# arcaduinome.net
KiCad netlist of a schematic drawn in EAGLE
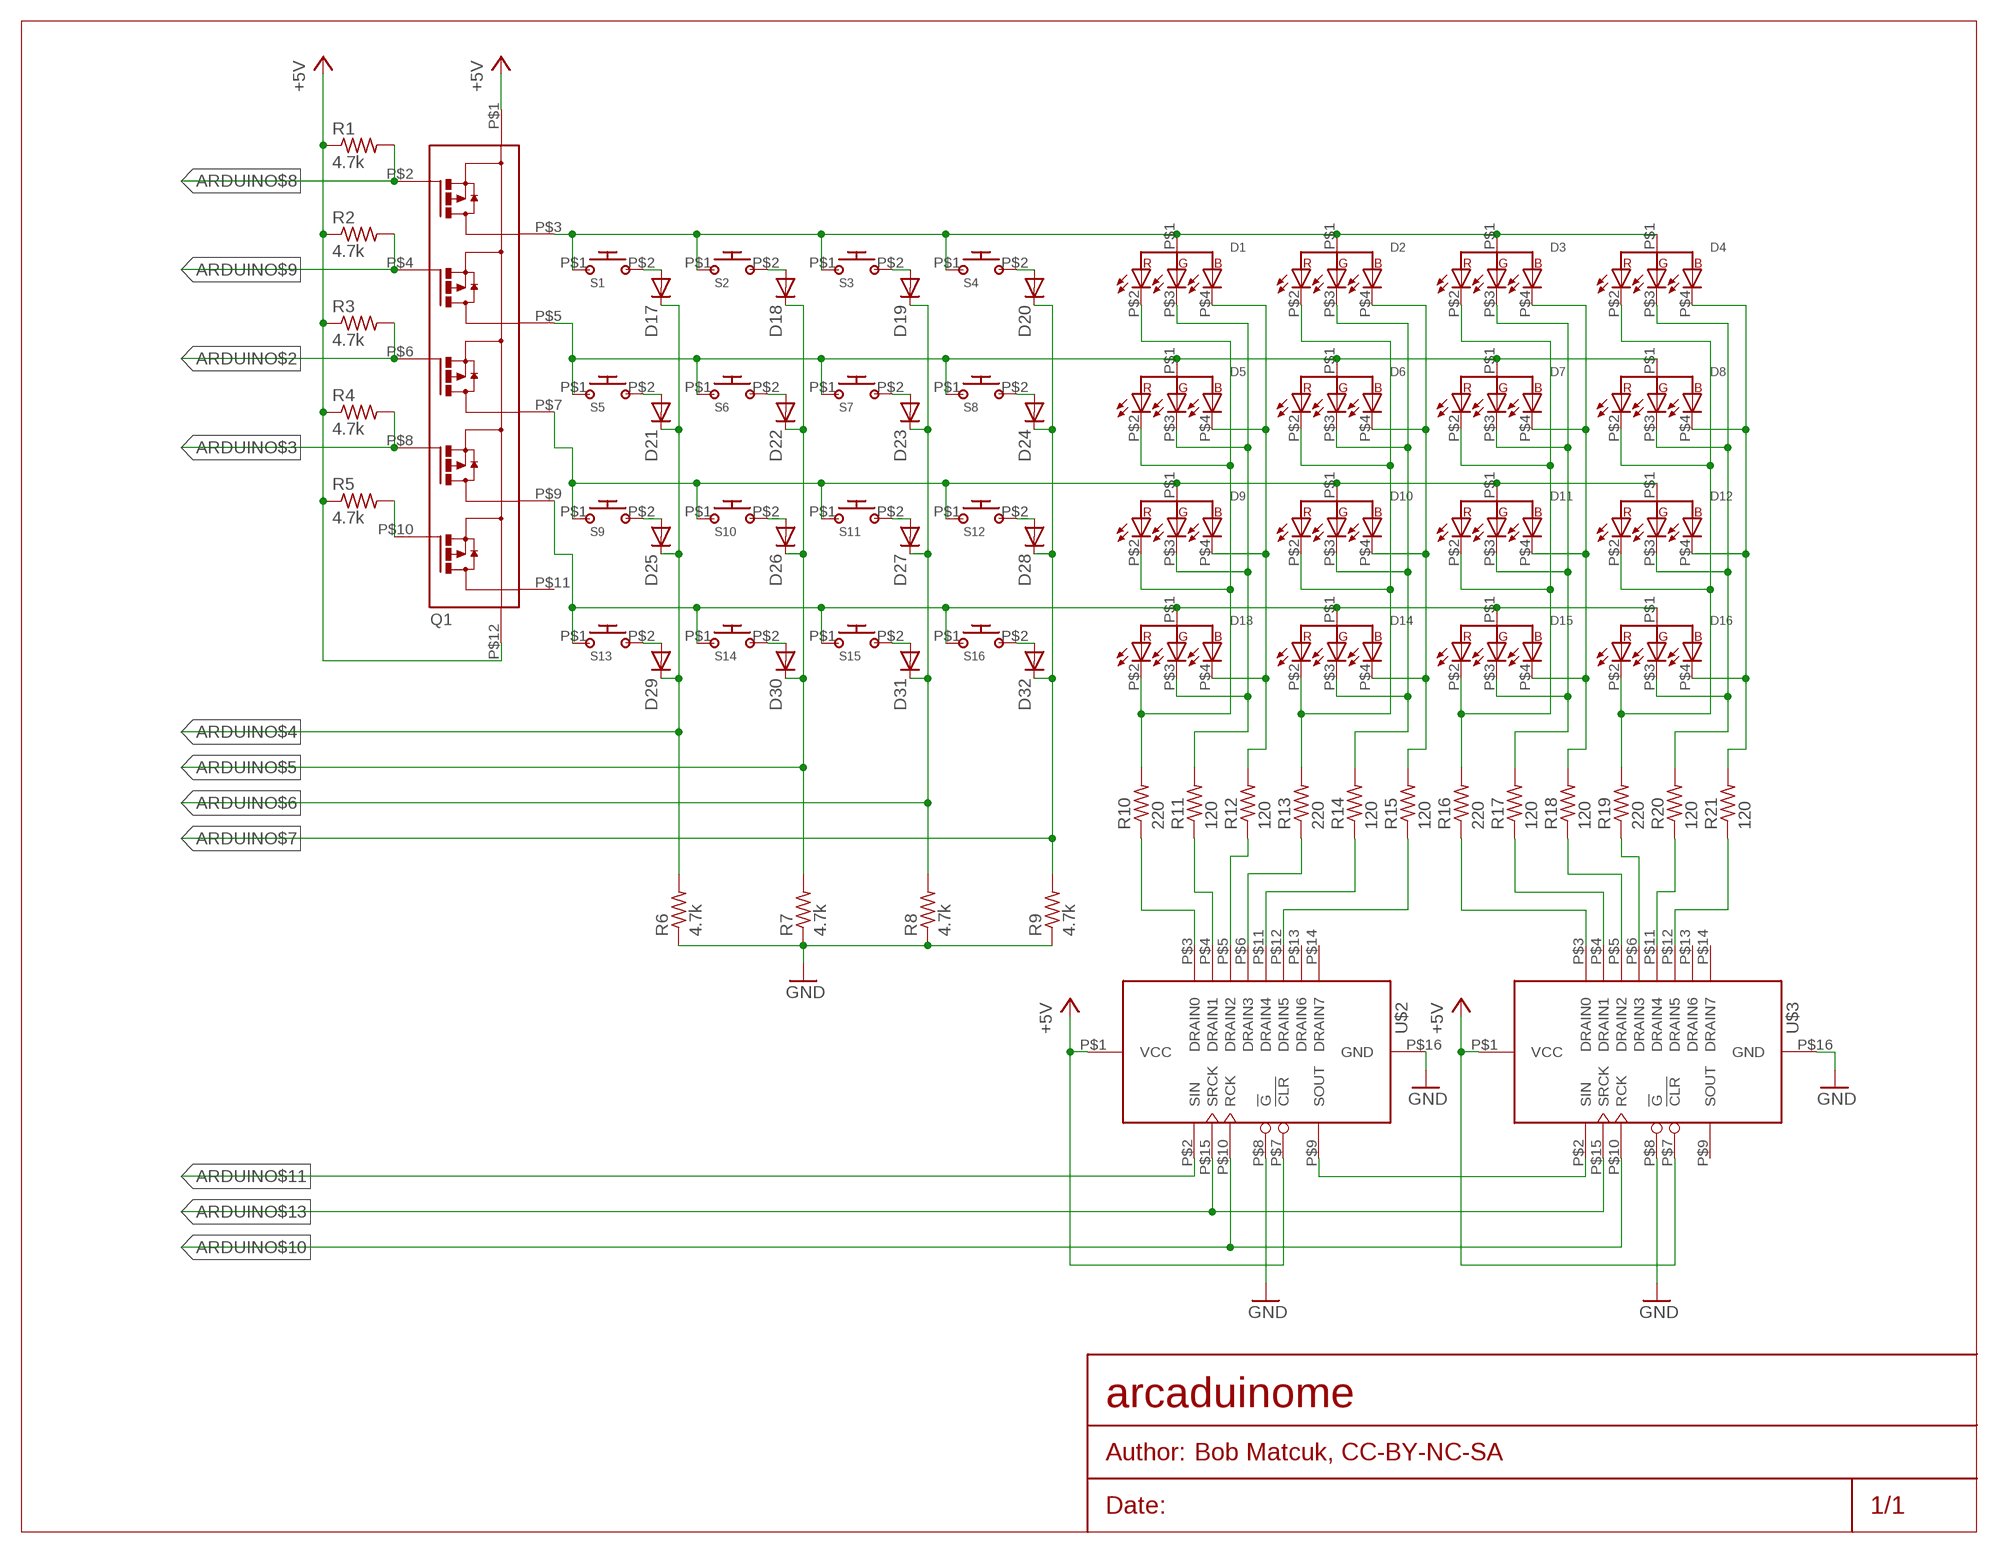
[diagram p0: schematic, sheet 1]

(export (version "E")
  (design (tool "Eeschema 10.0.6"))
  (components
    (comp (ref "D1")
      (value "FD-5WSRGB-A")
      (footprint "eagle-import:5MM_RGB_LED")
      (libsource (lib "eagle-import") (part "FD-5WSRGB-A"))
    )
    (comp (ref "D2")
      (value "FD-5WSRGB-A")
      (footprint "eagle-import:5MM_RGB_LED")
      (libsource (lib "eagle-import") (part "FD-5WSRGB-A"))
    )
    (comp (ref "D3")
      (value "FD-5WSRGB-A")
      (footprint "eagle-import:5MM_RGB_LED")
      (libsource (lib "eagle-import") (part "FD-5WSRGB-A"))
    )
    (comp (ref "D4")
      (value "FD-5WSRGB-A")
      (footprint "eagle-import:5MM_RGB_LED")
      (libsource (lib "eagle-import") (part "FD-5WSRGB-A"))
    )
    (comp (ref "D5")
      (value "FD-5WSRGB-A")
      (footprint "eagle-import:5MM_RGB_LED")
      (libsource (lib "eagle-import") (part "FD-5WSRGB-A"))
    )
    (comp (ref "D6")
      (value "FD-5WSRGB-A")
      (footprint "eagle-import:5MM_RGB_LED")
      (libsource (lib "eagle-import") (part "FD-5WSRGB-A"))
    )
    (comp (ref "D7")
      (value "FD-5WSRGB-A")
      (footprint "eagle-import:5MM_RGB_LED")
      (libsource (lib "eagle-import") (part "FD-5WSRGB-A"))
    )
    (comp (ref "D8")
      (value "FD-5WSRGB-A")
      (footprint "eagle-import:5MM_RGB_LED")
      (libsource (lib "eagle-import") (part "FD-5WSRGB-A"))
    )
    (comp (ref "D9")
      (value "FD-5WSRGB-A")
      (footprint "eagle-import:5MM_RGB_LED")
      (libsource (lib "eagle-import") (part "FD-5WSRGB-A"))
    )
    (comp (ref "D10")
      (value "FD-5WSRGB-A")
      (footprint "eagle-import:5MM_RGB_LED")
      (libsource (lib "eagle-import") (part "FD-5WSRGB-A"))
    )
    (comp (ref "D11")
      (value "FD-5WSRGB-A")
      (footprint "eagle-import:5MM_RGB_LED")
      (libsource (lib "eagle-import") (part "FD-5WSRGB-A"))
    )
    (comp (ref "D12")
      (value "FD-5WSRGB-A")
      (footprint "eagle-import:5MM_RGB_LED")
      (libsource (lib "eagle-import") (part "FD-5WSRGB-A"))
    )
    (comp (ref "D13")
      (value "FD-5WSRGB-A")
      (footprint "eagle-import:5MM_RGB_LED")
      (libsource (lib "eagle-import") (part "FD-5WSRGB-A"))
    )
    (comp (ref "D14")
      (value "FD-5WSRGB-A")
      (footprint "eagle-import:5MM_RGB_LED")
      (libsource (lib "eagle-import") (part "FD-5WSRGB-A"))
    )
    (comp (ref "D15")
      (value "FD-5WSRGB-A")
      (footprint "eagle-import:5MM_RGB_LED")
      (libsource (lib "eagle-import") (part "FD-5WSRGB-A"))
    )
    (comp (ref "D16")
      (value "FD-5WSRGB-A")
      (footprint "eagle-import:5MM_RGB_LED")
      (libsource (lib "eagle-import") (part "FD-5WSRGB-A"))
    )
    (comp (ref "D17")
      (value "1N4148DO35-7")
      (footprint "eagle-import:DO35-7")
      (libsource (lib "eagle-import") (part "1N4148DO35-7"))
    )
    (comp (ref "D18")
      (value "1N4148DO35-7")
      (footprint "eagle-import:DO35-7")
      (libsource (lib "eagle-import") (part "1N4148DO35-7"))
    )
    (comp (ref "D19")
      (value "1N4148DO35-7")
      (footprint "eagle-import:DO35-7")
      (libsource (lib "eagle-import") (part "1N4148DO35-7"))
    )
    (comp (ref "D20")
      (value "1N4148DO35-7")
      (footprint "eagle-import:DO35-7")
      (libsource (lib "eagle-import") (part "1N4148DO35-7"))
    )
    (comp (ref "D21")
      (value "1N4148DO35-7")
      (footprint "eagle-import:DO35-7")
      (libsource (lib "eagle-import") (part "1N4148DO35-7"))
    )
    (comp (ref "D22")
      (value "1N4148DO35-7")
      (footprint "eagle-import:DO35-7")
      (libsource (lib "eagle-import") (part "1N4148DO35-7"))
    )
    (comp (ref "D23")
      (value "1N4148DO35-7")
      (footprint "eagle-import:DO35-7")
      (libsource (lib "eagle-import") (part "1N4148DO35-7"))
    )
    (comp (ref "D24")
      (value "1N4148DO35-7")
      (footprint "eagle-import:DO35-7")
      (libsource (lib "eagle-import") (part "1N4148DO35-7"))
    )
    (comp (ref "D25")
      (value "1N4148DO35-7")
      (footprint "eagle-import:DO35-7")
      (libsource (lib "eagle-import") (part "1N4148DO35-7"))
    )
    (comp (ref "D26")
      (value "1N4148DO35-7")
      (footprint "eagle-import:DO35-7")
      (libsource (lib "eagle-import") (part "1N4148DO35-7"))
    )
    (comp (ref "D27")
      (value "1N4148DO35-7")
      (footprint "eagle-import:DO35-7")
      (libsource (lib "eagle-import") (part "1N4148DO35-7"))
    )
    (comp (ref "D28")
      (value "1N4148DO35-7")
      (footprint "eagle-import:DO35-7")
      (libsource (lib "eagle-import") (part "1N4148DO35-7"))
    )
    (comp (ref "D29")
      (value "1N4148DO35-7")
      (footprint "eagle-import:DO35-7")
      (libsource (lib "eagle-import") (part "1N4148DO35-7"))
    )
    (comp (ref "D30")
      (value "1N4148DO35-7")
      (footprint "eagle-import:DO35-7")
      (libsource (lib "eagle-import") (part "1N4148DO35-7"))
    )
    (comp (ref "D31")
      (value "1N4148DO35-7")
      (footprint "eagle-import:DO35-7")
      (libsource (lib "eagle-import") (part "1N4148DO35-7"))
    )
    (comp (ref "D32")
      (value "1N4148DO35-7")
      (footprint "eagle-import:DO35-7")
      (libsource (lib "eagle-import") (part "1N4148DO35-7"))
    )
    (comp (ref "Q1")
      (value "SLA5086")
      (footprint "eagle-import:SLA12")
      (libsource (lib "eagle-import") (part "SLA5086"))
    )
    (comp (ref "R1")
      (value "4.7k")
      (footprint "eagle-import:0207_10")
      (libsource (lib "eagle-import") (part "R-US_0207/10"))
    )
    (comp (ref "R2")
      (value "4.7k")
      (footprint "eagle-import:0207_10")
      (libsource (lib "eagle-import") (part "R-US_0207/10"))
    )
    (comp (ref "R3")
      (value "4.7k")
      (footprint "eagle-import:0207_10")
      (libsource (lib "eagle-import") (part "R-US_0207/10"))
    )
    (comp (ref "R4")
      (value "4.7k")
      (footprint "eagle-import:0207_10")
      (libsource (lib "eagle-import") (part "R-US_0207/10"))
    )
    (comp (ref "R5")
      (value "4.7k")
      (footprint "eagle-import:0207_10")
      (libsource (lib "eagle-import") (part "R-US_0207/10"))
    )
    (comp (ref "R6")
      (value "4.7k")
      (footprint "eagle-import:0207_10")
      (libsource (lib "eagle-import") (part "R-US_0207/10"))
    )
    (comp (ref "R7")
      (value "4.7k")
      (footprint "eagle-import:0207_10")
      (libsource (lib "eagle-import") (part "R-US_0207/10"))
    )
    (comp (ref "R8")
      (value "4.7k")
      (footprint "eagle-import:0207_10")
      (libsource (lib "eagle-import") (part "R-US_0207/10"))
    )
    (comp (ref "R9")
      (value "4.7k")
      (footprint "eagle-import:0207_10")
      (libsource (lib "eagle-import") (part "R-US_0207/10"))
    )
    (comp (ref "R10")
      (value "220")
      (footprint "eagle-import:0207_7")
      (libsource (lib "eagle-import") (part "R-US_0207/7"))
    )
    (comp (ref "R11")
      (value "120")
      (footprint "eagle-import:0204_5")
      (libsource (lib "eagle-import") (part "R-US_0204/5"))
    )
    (comp (ref "R12")
      (value "120")
      (footprint "eagle-import:0204_5")
      (libsource (lib "eagle-import") (part "R-US_0204/5"))
    )
    (comp (ref "R13")
      (value "220")
      (footprint "eagle-import:0207_7")
      (libsource (lib "eagle-import") (part "R-US_0207/7"))
    )
    (comp (ref "R14")
      (value "120")
      (footprint "eagle-import:0204_5")
      (libsource (lib "eagle-import") (part "R-US_0204/5"))
    )
    (comp (ref "R15")
      (value "120")
      (footprint "eagle-import:0204_5")
      (libsource (lib "eagle-import") (part "R-US_0204/5"))
    )
    (comp (ref "R16")
      (value "220")
      (footprint "eagle-import:0207_7")
      (libsource (lib "eagle-import") (part "R-US_0207/7"))
    )
    (comp (ref "R17")
      (value "120")
      (footprint "eagle-import:0204_5")
      (libsource (lib "eagle-import") (part "R-US_0204/5"))
    )
    (comp (ref "R18")
      (value "120")
      (footprint "eagle-import:0204_5")
      (libsource (lib "eagle-import") (part "R-US_0204/5"))
    )
    (comp (ref "R19")
      (value "220")
      (footprint "eagle-import:0207_7")
      (libsource (lib "eagle-import") (part "R-US_0207/7"))
    )
    (comp (ref "R20")
      (value "120")
      (footprint "eagle-import:0204_5")
      (libsource (lib "eagle-import") (part "R-US_0204/5"))
    )
    (comp (ref "R21")
      (value "120")
      (footprint "eagle-import:0204_5")
      (libsource (lib "eagle-import") (part "R-US_0204/5"))
    )
    (comp (ref "S1")
      (value "SANWA_OBSC_24_CW")
      (footprint "eagle-import:SANWA_24MM")
      (libsource (lib "eagle-import") (part "SANWA_OBSC_24_CW"))
    )
    (comp (ref "S2")
      (value "SANWA_OBSC_24_CW")
      (footprint "eagle-import:SANWA_24MM")
      (libsource (lib "eagle-import") (part "SANWA_OBSC_24_CW"))
    )
    (comp (ref "S3")
      (value "SANWA_OBSC_24_CW")
      (footprint "eagle-import:SANWA_24MM")
      (libsource (lib "eagle-import") (part "SANWA_OBSC_24_CW"))
    )
    (comp (ref "S4")
      (value "SANWA_OBSC_24_CW")
      (footprint "eagle-import:SANWA_24MM")
      (libsource (lib "eagle-import") (part "SANWA_OBSC_24_CW"))
    )
    (comp (ref "S5")
      (value "SANWA_OBSC_24_CW")
      (footprint "eagle-import:SANWA_24MM")
      (libsource (lib "eagle-import") (part "SANWA_OBSC_24_CW"))
    )
    (comp (ref "S6")
      (value "SANWA_OBSC_24_CW")
      (footprint "eagle-import:SANWA_24MM")
      (libsource (lib "eagle-import") (part "SANWA_OBSC_24_CW"))
    )
    (comp (ref "S7")
      (value "SANWA_OBSC_24_CW")
      (footprint "eagle-import:SANWA_24MM")
      (libsource (lib "eagle-import") (part "SANWA_OBSC_24_CW"))
    )
    (comp (ref "S8")
      (value "SANWA_OBSC_24_CW")
      (footprint "eagle-import:SANWA_24MM")
      (libsource (lib "eagle-import") (part "SANWA_OBSC_24_CW"))
    )
    (comp (ref "S9")
      (value "SANWA_OBSC_24_CW")
      (footprint "eagle-import:SANWA_24MM")
      (libsource (lib "eagle-import") (part "SANWA_OBSC_24_CW"))
    )
    (comp (ref "S10")
      (value "SANWA_OBSC_24_CW")
      (footprint "eagle-import:SANWA_24MM")
      (libsource (lib "eagle-import") (part "SANWA_OBSC_24_CW"))
    )
    (comp (ref "S11")
      (value "SANWA_OBSC_24_CW")
      (footprint "eagle-import:SANWA_24MM")
      (libsource (lib "eagle-import") (part "SANWA_OBSC_24_CW"))
    )
    (comp (ref "S12")
      (value "SANWA_OBSC_24_CW")
      (footprint "eagle-import:SANWA_24MM")
      (libsource (lib "eagle-import") (part "SANWA_OBSC_24_CW"))
    )
    (comp (ref "S13")
      (value "SANWA_OBSC_24_CW")
      (footprint "eagle-import:SANWA_24MM")
      (libsource (lib "eagle-import") (part "SANWA_OBSC_24_CW"))
    )
    (comp (ref "S14")
      (value "SANWA_OBSC_24_CW")
      (footprint "eagle-import:SANWA_24MM")
      (libsource (lib "eagle-import") (part "SANWA_OBSC_24_CW"))
    )
    (comp (ref "S15")
      (value "SANWA_OBSC_24_CW")
      (footprint "eagle-import:SANWA_24MM")
      (libsource (lib "eagle-import") (part "SANWA_OBSC_24_CW"))
    )
    (comp (ref "S16")
      (value "SANWA_OBSC_24_CW")
      (footprint "eagle-import:SANWA_24MM")
      (libsource (lib "eagle-import") (part "SANWA_OBSC_24_CW"))
    )
    (comp (ref "U$2")
      (value "STPIC6D595")
      (footprint "eagle-import:DIP16")
      (libsource (lib "eagle-import") (part "STPIC6D595"))
    )
    (comp (ref "U$3")
      (value "STPIC6D595")
      (footprint "eagle-import:DIP16")
      (libsource (lib "eagle-import") (part "STPIC6D595"))
    )
  )
  (nets
    (net (code "1") (name "+5V") (class "Default")
      (node (ref "Q1") (pin "P$1") (pinfunction "S_P$1") (pintype "passive"))
      (node (ref "Q1") (pin "P$12") (pinfunction "S_P$12") (pintype "passive"))
      (node (ref "R1") (pin "1") (pinfunction "1_1") (pintype "passive"))
      (node (ref "R2") (pin "1") (pinfunction "1_1") (pintype "passive"))
      (node (ref "R3") (pin "1") (pinfunction "1_1") (pintype "passive"))
      (node (ref "R4") (pin "1") (pinfunction "1_1") (pintype "passive"))
      (node (ref "R5") (pin "1") (pinfunction "1_1") (pintype "passive"))
      (node (ref "U$2") (pin "P$1") (pinfunction "VCC_P$1") (pintype "power_in"))
      (node (ref "U$2") (pin "P$7") (pinfunction "~{CLR}_P$7") (pintype "bidirectional"))
      (node (ref "U$3") (pin "P$1") (pinfunction "VCC_P$1") (pintype "power_in"))
      (node (ref "U$3") (pin "P$7") (pinfunction "~{CLR}_P$7") (pintype "bidirectional"))
    )
    (net (code "2") (name "ARDUINO$2") (class "Default")
      (node (ref "Q1") (pin "P$6") (pinfunction "G$3_P$6") (pintype "passive"))
      (node (ref "R3") (pin "2") (pinfunction "2_2") (pintype "passive"))
    )
    (net (code "3") (name "ARDUINO$3") (class "Default")
      (node (ref "Q1") (pin "P$8") (pinfunction "G$4_P$8") (pintype "passive"))
      (node (ref "R4") (pin "2") (pinfunction "2_2") (pintype "passive"))
    )
    (net (code "4") (name "ARDUINO$4") (class "Default")
      (node (ref "D17") (pin "C") (pinfunction "C_C") (pintype "passive"))
      (node (ref "D21") (pin "C") (pinfunction "C_C") (pintype "passive"))
      (node (ref "D25") (pin "C") (pinfunction "C_C") (pintype "passive"))
      (node (ref "D29") (pin "C") (pinfunction "C_C") (pintype "passive"))
      (node (ref "R6") (pin "2") (pinfunction "2_2") (pintype "passive"))
    )
    (net (code "5") (name "ARDUINO$5") (class "Default")
      (node (ref "D18") (pin "C") (pinfunction "C_C") (pintype "passive"))
      (node (ref "D22") (pin "C") (pinfunction "C_C") (pintype "passive"))
      (node (ref "D26") (pin "C") (pinfunction "C_C") (pintype "passive"))
      (node (ref "D30") (pin "C") (pinfunction "C_C") (pintype "passive"))
      (node (ref "R7") (pin "2") (pinfunction "2_2") (pintype "passive"))
    )
    (net (code "6") (name "ARDUINO$6") (class "Default")
      (node (ref "D19") (pin "C") (pinfunction "C_C") (pintype "passive"))
      (node (ref "D23") (pin "C") (pinfunction "C_C") (pintype "passive"))
      (node (ref "D27") (pin "C") (pinfunction "C_C") (pintype "passive"))
      (node (ref "D31") (pin "C") (pinfunction "C_C") (pintype "passive"))
      (node (ref "R8") (pin "2") (pinfunction "2_2") (pintype "passive"))
    )
    (net (code "7") (name "ARDUINO$7") (class "Default")
      (node (ref "D20") (pin "C") (pinfunction "C_C") (pintype "passive"))
      (node (ref "D24") (pin "C") (pinfunction "C_C") (pintype "passive"))
      (node (ref "D28") (pin "C") (pinfunction "C_C") (pintype "passive"))
      (node (ref "D32") (pin "C") (pinfunction "C_C") (pintype "passive"))
      (node (ref "R9") (pin "2") (pinfunction "2_2") (pintype "passive"))
    )
    (net (code "8") (name "ARDUINO$8") (class "Default")
      (node (ref "Q1") (pin "P$2") (pinfunction "G$1_P$2") (pintype "passive"))
      (node (ref "R1") (pin "2") (pinfunction "2_2") (pintype "passive"))
    )
    (net (code "9") (name "ARDUINO$9") (class "Default")
      (node (ref "Q1") (pin "P$4") (pinfunction "G$2_P$4") (pintype "passive"))
      (node (ref "R2") (pin "2") (pinfunction "2_2") (pintype "passive"))
    )
    (net (code "10") (name "ARDUINO$10") (class "Default")
      (node (ref "U$2") (pin "P$10") (pinfunction "RCK_P$10") (pintype "input"))
      (node (ref "U$3") (pin "P$10") (pinfunction "RCK_P$10") (pintype "input"))
    )
    (net (code "11") (name "ARDUINO$11") (class "Default")
      (node (ref "U$2") (pin "P$2") (pinfunction "SIN_P$2") (pintype "input"))
    )
    (net (code "12") (name "ARDUINO$13") (class "Default")
      (node (ref "U$2") (pin "P$15") (pinfunction "SRCK_P$15") (pintype "input"))
      (node (ref "U$3") (pin "P$15") (pinfunction "SRCK_P$15") (pintype "input"))
    )
    (net (code "13") (name "GND") (class "Default")
      (node (ref "R6") (pin "1") (pinfunction "1_1") (pintype "passive"))
      (node (ref "R7") (pin "1") (pinfunction "1_1") (pintype "passive"))
      (node (ref "R8") (pin "1") (pinfunction "1_1") (pintype "passive"))
      (node (ref "R9") (pin "1") (pinfunction "1_1") (pintype "passive"))
      (node (ref "U$2") (pin "P$16") (pinfunction "GND_P$16") (pintype "power_in"))
      (node (ref "U$2") (pin "P$8") (pinfunction "~{G}_P$8") (pintype "bidirectional"))
      (node (ref "U$3") (pin "P$16") (pinfunction "GND_P$16") (pintype "power_in"))
      (node (ref "U$3") (pin "P$8") (pinfunction "~{G}_P$8") (pintype "bidirectional"))
    )
    (net (code "14") (name "Net-(D1-ANODE)") (class "Default")
      (node (ref "D1") (pin "P$1") (pinfunction "ANODE_P$1") (pintype "passive"))
      (node (ref "D2") (pin "P$1") (pinfunction "ANODE_P$1") (pintype "passive"))
      (node (ref "D3") (pin "P$1") (pinfunction "ANODE_P$1") (pintype "passive"))
      (node (ref "D4") (pin "P$1") (pinfunction "ANODE_P$1") (pintype "passive"))
      (node (ref "Q1") (pin "P$3") (pinfunction "D$1_P$3") (pintype "passive"))
      (node (ref "S1") (pin "P$1") (pinfunction "P$1_P$1") (pintype "passive"))
      (node (ref "S2") (pin "P$1") (pinfunction "P$1_P$1") (pintype "passive"))
      (node (ref "S3") (pin "P$1") (pinfunction "P$1_P$1") (pintype "passive"))
      (node (ref "S4") (pin "P$1") (pinfunction "P$1_P$1") (pintype "passive"))
    )
    (net (code "15") (name "Net-(D1-B)") (class "Default")
      (node (ref "D1") (pin "P$4") (pinfunction "B_P$4") (pintype "passive"))
      (node (ref "D13") (pin "P$4") (pinfunction "B_P$4") (pintype "passive"))
      (node (ref "D5") (pin "P$4") (pinfunction "B_P$4") (pintype "passive"))
      (node (ref "D9") (pin "P$4") (pinfunction "B_P$4") (pintype "passive"))
      (node (ref "R12") (pin "2") (pinfunction "2_2") (pintype "passive"))
    )
    (net (code "16") (name "Net-(D1-G)") (class "Default")
      (node (ref "D1") (pin "P$3") (pinfunction "G_P$3") (pintype "passive"))
      (node (ref "D13") (pin "P$3") (pinfunction "G_P$3") (pintype "passive"))
      (node (ref "D5") (pin "P$3") (pinfunction "G_P$3") (pintype "passive"))
      (node (ref "D9") (pin "P$3") (pinfunction "G_P$3") (pintype "passive"))
      (node (ref "R11") (pin "2") (pinfunction "2_2") (pintype "passive"))
    )
    (net (code "17") (name "Net-(D1-R)") (class "Default")
      (node (ref "D1") (pin "P$2") (pinfunction "R_P$2") (pintype "passive"))
      (node (ref "D13") (pin "P$2") (pinfunction "R_P$2") (pintype "passive"))
      (node (ref "D5") (pin "P$2") (pinfunction "R_P$2") (pintype "passive"))
      (node (ref "D9") (pin "P$2") (pinfunction "R_P$2") (pintype "passive"))
      (node (ref "R10") (pin "2") (pinfunction "2_2") (pintype "passive"))
    )
    (net (code "18") (name "Net-(D5-ANODE)") (class "Default")
      (node (ref "D5") (pin "P$1") (pinfunction "ANODE_P$1") (pintype "passive"))
      (node (ref "D6") (pin "P$1") (pinfunction "ANODE_P$1") (pintype "passive"))
      (node (ref "D7") (pin "P$1") (pinfunction "ANODE_P$1") (pintype "passive"))
      (node (ref "D8") (pin "P$1") (pinfunction "ANODE_P$1") (pintype "passive"))
      (node (ref "Q1") (pin "P$5") (pinfunction "D$2_P$5") (pintype "passive"))
      (node (ref "S5") (pin "P$1") (pinfunction "P$1_P$1") (pintype "passive"))
      (node (ref "S6") (pin "P$1") (pinfunction "P$1_P$1") (pintype "passive"))
      (node (ref "S7") (pin "P$1") (pinfunction "P$1_P$1") (pintype "passive"))
      (node (ref "S8") (pin "P$1") (pinfunction "P$1_P$1") (pintype "passive"))
    )
    (net (code "19") (name "Net-(D10-ANODE)") (class "Default")
      (node (ref "D10") (pin "P$1") (pinfunction "ANODE_P$1") (pintype "passive"))
      (node (ref "D11") (pin "P$1") (pinfunction "ANODE_P$1") (pintype "passive"))
      (node (ref "D12") (pin "P$1") (pinfunction "ANODE_P$1") (pintype "passive"))
      (node (ref "D9") (pin "P$1") (pinfunction "ANODE_P$1") (pintype "passive"))
      (node (ref "Q1") (pin "P$7") (pinfunction "D$3_P$7") (pintype "passive"))
      (node (ref "S10") (pin "P$1") (pinfunction "P$1_P$1") (pintype "passive"))
      (node (ref "S11") (pin "P$1") (pinfunction "P$1_P$1") (pintype "passive"))
      (node (ref "S12") (pin "P$1") (pinfunction "P$1_P$1") (pintype "passive"))
      (node (ref "S9") (pin "P$1") (pinfunction "P$1_P$1") (pintype "passive"))
    )
    (net (code "20") (name "Net-(D10-B)") (class "Default")
      (node (ref "D10") (pin "P$4") (pinfunction "B_P$4") (pintype "passive"))
      (node (ref "D14") (pin "P$4") (pinfunction "B_P$4") (pintype "passive"))
      (node (ref "D2") (pin "P$4") (pinfunction "B_P$4") (pintype "passive"))
      (node (ref "D6") (pin "P$4") (pinfunction "B_P$4") (pintype "passive"))
      (node (ref "R15") (pin "2") (pinfunction "2_2") (pintype "passive"))
    )
    (net (code "21") (name "Net-(D10-G)") (class "Default")
      (node (ref "D10") (pin "P$3") (pinfunction "G_P$3") (pintype "passive"))
      (node (ref "D14") (pin "P$3") (pinfunction "G_P$3") (pintype "passive"))
      (node (ref "D2") (pin "P$3") (pinfunction "G_P$3") (pintype "passive"))
      (node (ref "D6") (pin "P$3") (pinfunction "G_P$3") (pintype "passive"))
      (node (ref "R14") (pin "2") (pinfunction "2_2") (pintype "passive"))
    )
    (net (code "22") (name "Net-(D10-R)") (class "Default")
      (node (ref "D10") (pin "P$2") (pinfunction "R_P$2") (pintype "passive"))
      (node (ref "D14") (pin "P$2") (pinfunction "R_P$2") (pintype "passive"))
      (node (ref "D2") (pin "P$2") (pinfunction "R_P$2") (pintype "passive"))
      (node (ref "D6") (pin "P$2") (pinfunction "R_P$2") (pintype "passive"))
      (node (ref "R13") (pin "2") (pinfunction "2_2") (pintype "passive"))
    )
    (net (code "23") (name "Net-(D11-B)") (class "Default")
      (node (ref "D11") (pin "P$4") (pinfunction "B_P$4") (pintype "passive"))
      (node (ref "D15") (pin "P$4") (pinfunction "B_P$4") (pintype "passive"))
      (node (ref "D3") (pin "P$4") (pinfunction "B_P$4") (pintype "passive"))
      (node (ref "D7") (pin "P$4") (pinfunction "B_P$4") (pintype "passive"))
      (node (ref "R18") (pin "2") (pinfunction "2_2") (pintype "passive"))
    )
    (net (code "24") (name "Net-(D11-G)") (class "Default")
      (node (ref "D11") (pin "P$3") (pinfunction "G_P$3") (pintype "passive"))
      (node (ref "D15") (pin "P$3") (pinfunction "G_P$3") (pintype "passive"))
      (node (ref "D3") (pin "P$3") (pinfunction "G_P$3") (pintype "passive"))
      (node (ref "D7") (pin "P$3") (pinfunction "G_P$3") (pintype "passive"))
      (node (ref "R17") (pin "2") (pinfunction "2_2") (pintype "passive"))
    )
    (net (code "25") (name "Net-(D11-R)") (class "Default")
      (node (ref "D11") (pin "P$2") (pinfunction "R_P$2") (pintype "passive"))
      (node (ref "D15") (pin "P$2") (pinfunction "R_P$2") (pintype "passive"))
      (node (ref "D3") (pin "P$2") (pinfunction "R_P$2") (pintype "passive"))
      (node (ref "D7") (pin "P$2") (pinfunction "R_P$2") (pintype "passive"))
      (node (ref "R16") (pin "2") (pinfunction "2_2") (pintype "passive"))
    )
    (net (code "26") (name "Net-(D12-B)") (class "Default")
      (node (ref "D12") (pin "P$4") (pinfunction "B_P$4") (pintype "passive"))
      (node (ref "D16") (pin "P$4") (pinfunction "B_P$4") (pintype "passive"))
      (node (ref "D4") (pin "P$4") (pinfunction "B_P$4") (pintype "passive"))
      (node (ref "D8") (pin "P$4") (pinfunction "B_P$4") (pintype "passive"))
      (node (ref "R21") (pin "2") (pinfunction "2_2") (pintype "passive"))
    )
    (net (code "27") (name "Net-(D12-G)") (class "Default")
      (node (ref "D12") (pin "P$3") (pinfunction "G_P$3") (pintype "passive"))
      (node (ref "D16") (pin "P$3") (pinfunction "G_P$3") (pintype "passive"))
      (node (ref "D4") (pin "P$3") (pinfunction "G_P$3") (pintype "passive"))
      (node (ref "D8") (pin "P$3") (pinfunction "G_P$3") (pintype "passive"))
      (node (ref "R20") (pin "2") (pinfunction "2_2") (pintype "passive"))
    )
    (net (code "28") (name "Net-(D12-R)") (class "Default")
      (node (ref "D12") (pin "P$2") (pinfunction "R_P$2") (pintype "passive"))
      (node (ref "D16") (pin "P$2") (pinfunction "R_P$2") (pintype "passive"))
      (node (ref "D4") (pin "P$2") (pinfunction "R_P$2") (pintype "passive"))
      (node (ref "D8") (pin "P$2") (pinfunction "R_P$2") (pintype "passive"))
      (node (ref "R19") (pin "2") (pinfunction "2_2") (pintype "passive"))
    )
    (net (code "29") (name "Net-(D13-ANODE)") (class "Default")
      (node (ref "D13") (pin "P$1") (pinfunction "ANODE_P$1") (pintype "passive"))
      (node (ref "D14") (pin "P$1") (pinfunction "ANODE_P$1") (pintype "passive"))
      (node (ref "D15") (pin "P$1") (pinfunction "ANODE_P$1") (pintype "passive"))
      (node (ref "D16") (pin "P$1") (pinfunction "ANODE_P$1") (pintype "passive"))
      (node (ref "Q1") (pin "P$9") (pinfunction "D$4_P$9") (pintype "passive"))
      (node (ref "S13") (pin "P$1") (pinfunction "P$1_P$1") (pintype "passive"))
      (node (ref "S14") (pin "P$1") (pinfunction "P$1_P$1") (pintype "passive"))
      (node (ref "S15") (pin "P$1") (pinfunction "P$1_P$1") (pintype "passive"))
      (node (ref "S16") (pin "P$1") (pinfunction "P$1_P$1") (pintype "passive"))
    )
    (net (code "30") (name "Net-(D17-PadA)") (class "Default")
      (node (ref "D17") (pin "A") (pinfunction "A_A") (pintype "passive"))
      (node (ref "S1") (pin "P$2") (pinfunction "P$2_P$2") (pintype "passive"))
    )
    (net (code "31") (name "Net-(D18-PadA)") (class "Default")
      (node (ref "D18") (pin "A") (pinfunction "A_A") (pintype "passive"))
      (node (ref "S2") (pin "P$2") (pinfunction "P$2_P$2") (pintype "passive"))
    )
    (net (code "32") (name "Net-(D19-PadA)") (class "Default")
      (node (ref "D19") (pin "A") (pinfunction "A_A") (pintype "passive"))
      (node (ref "S3") (pin "P$2") (pinfunction "P$2_P$2") (pintype "passive"))
    )
    (net (code "33") (name "Net-(D20-PadA)") (class "Default")
      (node (ref "D20") (pin "A") (pinfunction "A_A") (pintype "passive"))
      (node (ref "S4") (pin "P$2") (pinfunction "P$2_P$2") (pintype "passive"))
    )
    (net (code "34") (name "Net-(D21-PadA)") (class "Default")
      (node (ref "D21") (pin "A") (pinfunction "A_A") (pintype "passive"))
      (node (ref "S5") (pin "P$2") (pinfunction "P$2_P$2") (pintype "passive"))
    )
    (net (code "35") (name "Net-(D22-PadA)") (class "Default")
      (node (ref "D22") (pin "A") (pinfunction "A_A") (pintype "passive"))
      (node (ref "S6") (pin "P$2") (pinfunction "P$2_P$2") (pintype "passive"))
    )
    (net (code "36") (name "Net-(D23-PadA)") (class "Default")
      (node (ref "D23") (pin "A") (pinfunction "A_A") (pintype "passive"))
      (node (ref "S7") (pin "P$2") (pinfunction "P$2_P$2") (pintype "passive"))
    )
    (net (code "37") (name "Net-(D24-PadA)") (class "Default")
      (node (ref "D24") (pin "A") (pinfunction "A_A") (pintype "passive"))
      (node (ref "S8") (pin "P$2") (pinfunction "P$2_P$2") (pintype "passive"))
    )
    (net (code "38") (name "Net-(D25-PadA)") (class "Default")
      (node (ref "D25") (pin "A") (pinfunction "A_A") (pintype "passive"))
      (node (ref "S9") (pin "P$2") (pinfunction "P$2_P$2") (pintype "passive"))
    )
    (net (code "39") (name "Net-(D26-PadA)") (class "Default")
      (node (ref "D26") (pin "A") (pinfunction "A_A") (pintype "passive"))
      (node (ref "S10") (pin "P$2") (pinfunction "P$2_P$2") (pintype "passive"))
    )
    (net (code "40") (name "Net-(D27-PadA)") (class "Default")
      (node (ref "D27") (pin "A") (pinfunction "A_A") (pintype "passive"))
      (node (ref "S11") (pin "P$2") (pinfunction "P$2_P$2") (pintype "passive"))
    )
    (net (code "41") (name "Net-(D28-PadA)") (class "Default")
      (node (ref "D28") (pin "A") (pinfunction "A_A") (pintype "passive"))
      (node (ref "S12") (pin "P$2") (pinfunction "P$2_P$2") (pintype "passive"))
    )
    (net (code "42") (name "Net-(D29-PadA)") (class "Default")
      (node (ref "D29") (pin "A") (pinfunction "A_A") (pintype "passive"))
      (node (ref "S13") (pin "P$2") (pinfunction "P$2_P$2") (pintype "passive"))
    )
    (net (code "43") (name "Net-(D30-PadA)") (class "Default")
      (node (ref "D30") (pin "A") (pinfunction "A_A") (pintype "passive"))
      (node (ref "S14") (pin "P$2") (pinfunction "P$2_P$2") (pintype "passive"))
    )
    (net (code "44") (name "Net-(D31-PadA)") (class "Default")
      (node (ref "D31") (pin "A") (pinfunction "A_A") (pintype "passive"))
      (node (ref "S15") (pin "P$2") (pinfunction "P$2_P$2") (pintype "passive"))
    )
    (net (code "45") (name "Net-(D32-PadA)") (class "Default")
      (node (ref "D32") (pin "A") (pinfunction "A_A") (pintype "passive"))
      (node (ref "S16") (pin "P$2") (pinfunction "P$2_P$2") (pintype "passive"))
    )
    (net (code "46") (name "Net-(Q1-G$5)") (class "Default")
      (node (ref "Q1") (pin "P$10") (pinfunction "G$5_P$10") (pintype "passive"))
      (node (ref "R5") (pin "2") (pinfunction "2_2") (pintype "passive"))
    )
    (net (code "47") (name "Net-(U$2-DRAIN0)") (class "Default")
      (node (ref "R10") (pin "1") (pinfunction "1_1") (pintype "passive"))
      (node (ref "U$2") (pin "P$3") (pinfunction "DRAIN0_P$3") (pintype "open_collector"))
    )
    (net (code "48") (name "Net-(U$2-DRAIN1)") (class "Default")
      (node (ref "R11") (pin "1") (pinfunction "1_1") (pintype "passive"))
      (node (ref "U$2") (pin "P$4") (pinfunction "DRAIN1_P$4") (pintype "open_collector"))
    )
    (net (code "49") (name "Net-(U$2-DRAIN2)") (class "Default")
      (node (ref "R12") (pin "1") (pinfunction "1_1") (pintype "passive"))
      (node (ref "U$2") (pin "P$5") (pinfunction "DRAIN2_P$5") (pintype "open_collector"))
    )
    (net (code "50") (name "Net-(U$2-DRAIN3)") (class "Default")
      (node (ref "R13") (pin "1") (pinfunction "1_1") (pintype "passive"))
      (node (ref "U$2") (pin "P$6") (pinfunction "DRAIN3_P$6") (pintype "open_collector"))
    )
    (net (code "51") (name "Net-(U$2-DRAIN4)") (class "Default")
      (node (ref "R14") (pin "1") (pinfunction "1_1") (pintype "passive"))
      (node (ref "U$2") (pin "P$11") (pinfunction "DRAIN4_P$11") (pintype "open_collector"))
    )
    (net (code "52") (name "Net-(U$2-DRAIN5)") (class "Default")
      (node (ref "R15") (pin "1") (pinfunction "1_1") (pintype "passive"))
      (node (ref "U$2") (pin "P$12") (pinfunction "DRAIN5_P$12") (pintype "open_collector"))
    )
    (net (code "53") (name "Net-(U$2-SOUT)") (class "Default")
      (node (ref "U$2") (pin "P$9") (pinfunction "SOUT_P$9") (pintype "output"))
      (node (ref "U$3") (pin "P$2") (pinfunction "SIN_P$2") (pintype "input"))
    )
    (net (code "54") (name "Net-(U$3-DRAIN0)") (class "Default")
      (node (ref "R16") (pin "1") (pinfunction "1_1") (pintype "passive"))
      (node (ref "U$3") (pin "P$3") (pinfunction "DRAIN0_P$3") (pintype "open_collector"))
    )
    (net (code "55") (name "Net-(U$3-DRAIN1)") (class "Default")
      (node (ref "R17") (pin "1") (pinfunction "1_1") (pintype "passive"))
      (node (ref "U$3") (pin "P$4") (pinfunction "DRAIN1_P$4") (pintype "open_collector"))
    )
    (net (code "56") (name "Net-(U$3-DRAIN2)") (class "Default")
      (node (ref "R18") (pin "1") (pinfunction "1_1") (pintype "passive"))
      (node (ref "U$3") (pin "P$5") (pinfunction "DRAIN2_P$5") (pintype "open_collector"))
    )
    (net (code "57") (name "Net-(U$3-DRAIN3)") (class "Default")
      (node (ref "R19") (pin "1") (pinfunction "1_1") (pintype "passive"))
      (node (ref "U$3") (pin "P$6") (pinfunction "DRAIN3_P$6") (pintype "open_collector"))
    )
    (net (code "58") (name "Net-(U$3-DRAIN4)") (class "Default")
      (node (ref "R20") (pin "1") (pinfunction "1_1") (pintype "passive"))
      (node (ref "U$3") (pin "P$11") (pinfunction "DRAIN4_P$11") (pintype "open_collector"))
    )
    (net (code "59") (name "Net-(U$3-DRAIN5)") (class "Default")
      (node (ref "R21") (pin "1") (pinfunction "1_1") (pintype "passive"))
      (node (ref "U$3") (pin "P$12") (pinfunction "DRAIN5_P$12") (pintype "open_collector"))
    )
    (net (code "60") (name "unconnected-(Q1-D$5-PadP$11)") (class "Default")
      (node (ref "Q1") (pin "P$11") (pinfunction "D$5_P$11") (pintype "passive"))
    )
    (net (code "61") (name "unconnected-(U$2-DRAIN6-PadP$13)") (class "Default")
      (node (ref "U$2") (pin "P$13") (pinfunction "DRAIN6_P$13") (pintype "open_collector"))
    )
    (net (code "62") (name "unconnected-(U$2-DRAIN7-PadP$14)") (class "Default")
      (node (ref "U$2") (pin "P$14") (pinfunction "DRAIN7_P$14") (pintype "open_collector"))
    )
    (net (code "63") (name "unconnected-(U$3-DRAIN6-PadP$13)") (class "Default")
      (node (ref "U$3") (pin "P$13") (pinfunction "DRAIN6_P$13") (pintype "open_collector"))
    )
    (net (code "64") (name "unconnected-(U$3-DRAIN7-PadP$14)") (class "Default")
      (node (ref "U$3") (pin "P$14") (pinfunction "DRAIN7_P$14") (pintype "open_collector"))
    )
    (net (code "65") (name "unconnected-(U$3-SOUT-PadP$9)") (class "Default")
      (node (ref "U$3") (pin "P$9") (pinfunction "SOUT_P$9") (pintype "output"))
    )
  )
)
